# Adafruit_TMP117_angle.net
KiCad netlist of a schematic drawn in EAGLE
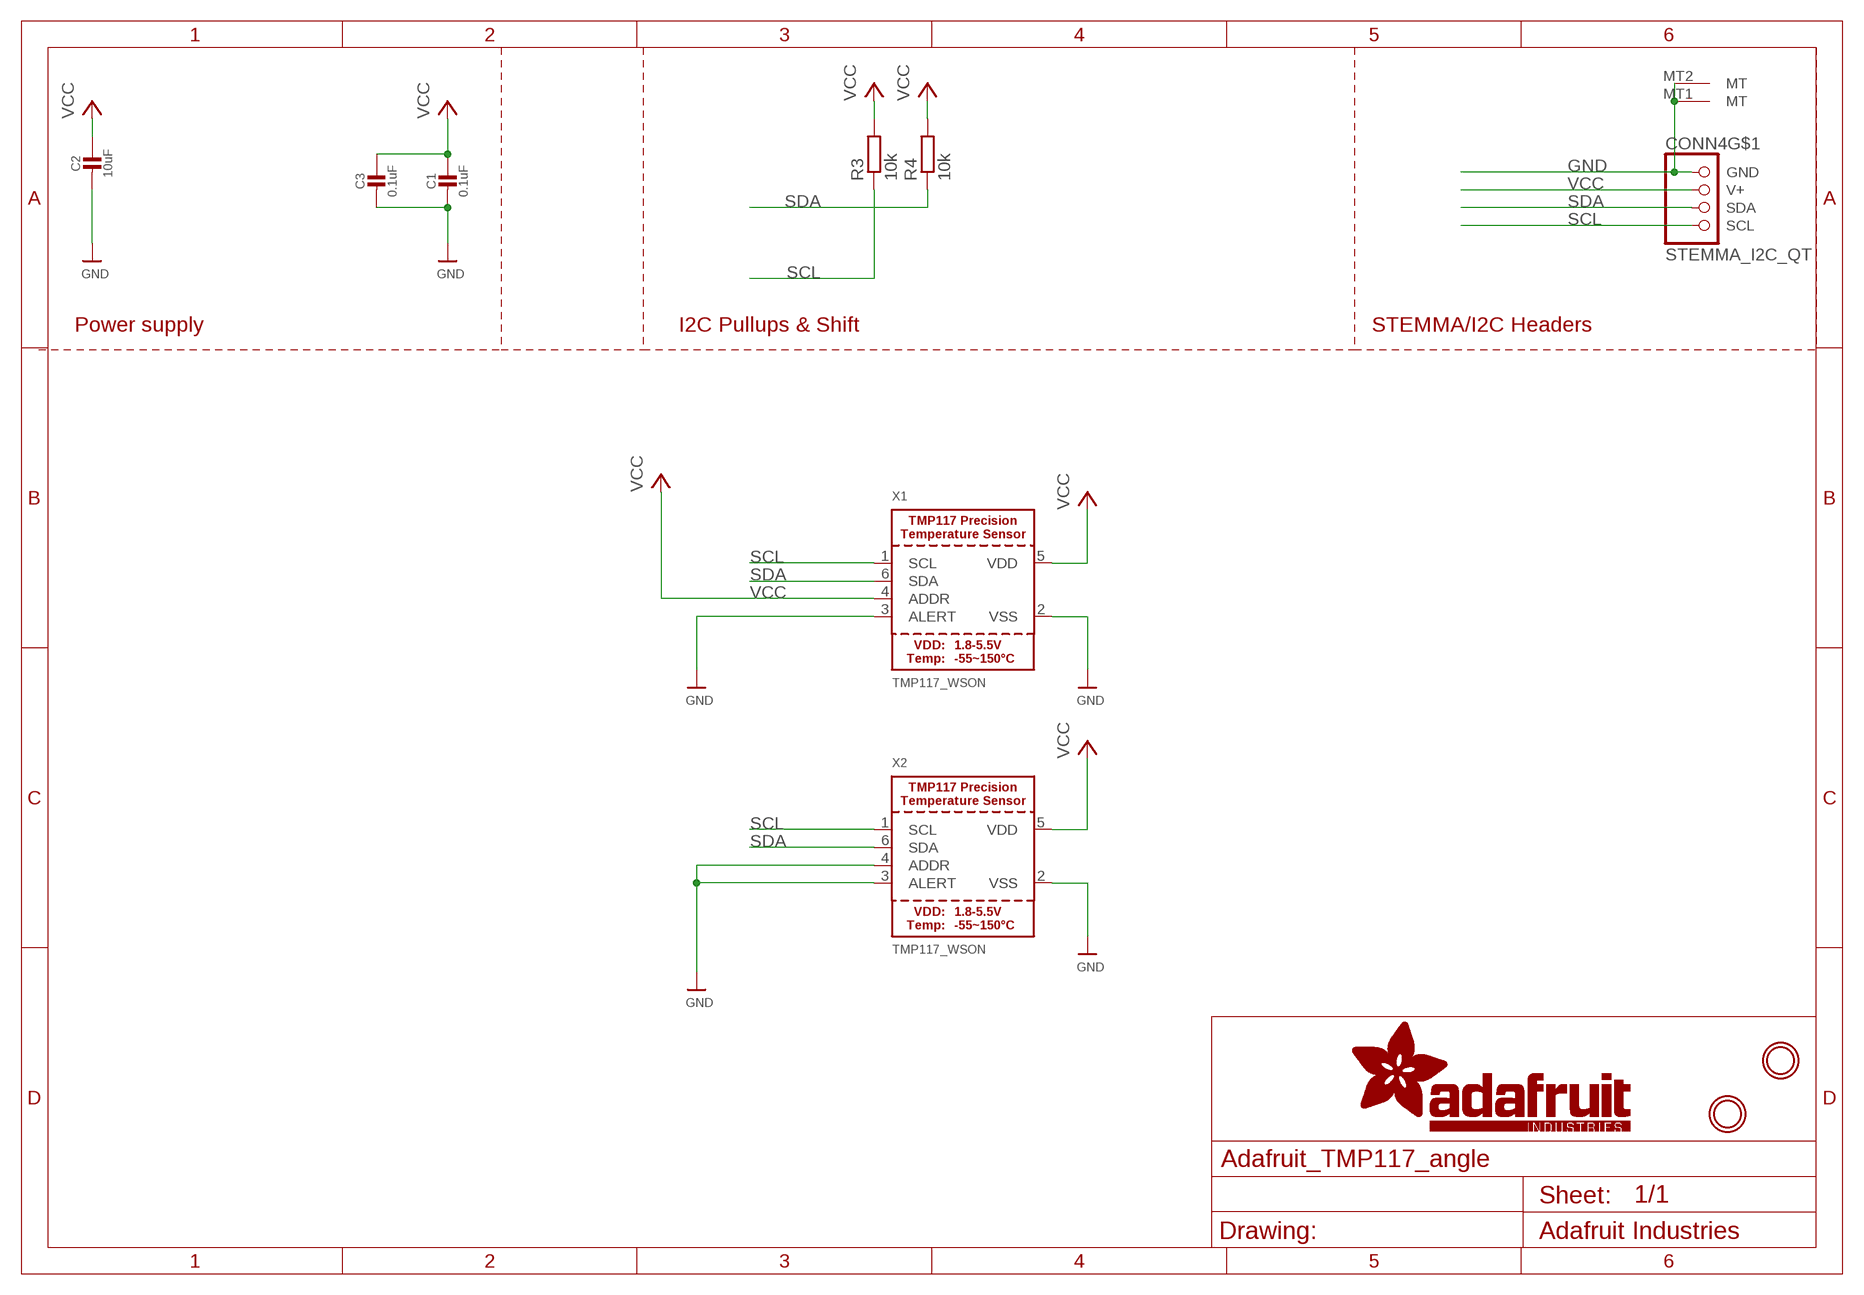
[diagram p0: schematic, sheet 1]

(export (version "E")
  (design (tool "Eeschema 10.0.6"))
  (components
    (comp (ref "C1")
      (value "0.1uF")
      (footprint "eagle-import:_0402")
      (libsource (lib "eagle-import") (part "CAP_CERAMIC_0402"))
    )
    (comp (ref "C2")
      (value "10uF")
      (footprint "eagle-import:_0603")
      (libsource (lib "eagle-import") (part "CAP_CERAMIC_0603"))
    )
    (comp (ref "C3")
      (value "0.1uF")
      (footprint "eagle-import:_0402")
      (libsource (lib "eagle-import") (part "CAP_CERAMIC_0402"))
    )
    (comp (ref "CONN4")
      (value "STEMMA_I2C_QT")
      (footprint "eagle-import:JST_SH4")
      (libsource (lib "eagle-import") (part "STEMMA_I2C_QT"))
    )
    (comp (ref "R3")
      (value "10k")
      (footprint "eagle-import:R0402")
      (libsource (lib "eagle-import") (part "R-EU_R0402"))
    )
    (comp (ref "R4")
      (value "10k")
      (footprint "eagle-import:R0402")
      (libsource (lib "eagle-import") (part "R-EU_R0402"))
    )
    (comp (ref "U$1")
      (value "MOUNTINGHOLE2.5")
      (footprint "eagle-import:MOUNTINGHOLE_2.5_PLATED")
      (libsource (lib "eagle-import") (part "MOUNTINGHOLE2.5"))
    )
    (comp (ref "U$19")
      (value "MOUNTINGHOLE2.5")
      (footprint "eagle-import:MOUNTINGHOLE_2.5_PLATED")
      (libsource (lib "eagle-import") (part "MOUNTINGHOLE2.5"))
    )
    (comp (ref "X1")
      (value "TMP117_WSON")
      (footprint "eagle-import:WSON-6")
      (libsource (lib "eagle-import") (part "TMP117_WSON"))
    )
    (comp (ref "X2")
      (value "TMP117_WSON")
      (footprint "eagle-import:WSON-6")
      (libsource (lib "eagle-import") (part "TMP117_WSON"))
    )
  )
  (nets
    (net (code "1") (name "/SCL") (class "Default")
      (node (ref "CONN4") (pin "4") (pinfunction "SCL_4") (pintype "passive"))
      (node (ref "R3") (pin "1") (pinfunction "1_1") (pintype "passive"))
      (node (ref "X1") (pin "1") (pinfunction "SCL_1") (pintype "bidirectional"))
      (node (ref "X2") (pin "1") (pinfunction "SCL_1") (pintype "bidirectional"))
    )
    (net (code "2") (name "/SDA") (class "Default")
      (node (ref "CONN4") (pin "3") (pinfunction "SDA_3") (pintype "passive"))
      (node (ref "R4") (pin "1") (pinfunction "1_1") (pintype "passive"))
      (node (ref "X1") (pin "6") (pinfunction "SDA_6") (pintype "bidirectional"))
      (node (ref "X2") (pin "6") (pinfunction "SDA_6") (pintype "bidirectional"))
    )
    (net (code "3") (name "GND") (class "Default")
      (node (ref "C1") (pin "2") (pinfunction "2_2") (pintype "passive"))
      (node (ref "C2") (pin "2") (pinfunction "2_2") (pintype "passive"))
      (node (ref "C3") (pin "2") (pinfunction "2_2") (pintype "passive"))
      (node (ref "CONN4") (pin "1") (pinfunction "GND_1") (pintype "passive"))
      (node (ref "CONN4") (pin "MT1") (pinfunction "MT_MT1") (pintype "bidirectional"))
      (node (ref "CONN4") (pin "MT2") (pinfunction "MT_MT2") (pintype "bidirectional"))
      (node (ref "X1") (pin "2") (pinfunction "VSS_2") (pintype "power_in"))
      (node (ref "X1") (pin "3") (pinfunction "ALERT_3") (pintype "output"))
      (node (ref "X2") (pin "2") (pinfunction "VSS_2") (pintype "power_in"))
      (node (ref "X2") (pin "3") (pinfunction "ALERT_3") (pintype "output"))
      (node (ref "X2") (pin "4") (pinfunction "ADDR_4") (pintype "input"))
    )
    (net (code "4") (name "VCC") (class "Default")
      (node (ref "C1") (pin "1") (pinfunction "1_1") (pintype "passive"))
      (node (ref "C2") (pin "1") (pinfunction "1_1") (pintype "passive"))
      (node (ref "C3") (pin "1") (pinfunction "1_1") (pintype "passive"))
      (node (ref "CONN4") (pin "2") (pinfunction "V+_2") (pintype "passive"))
      (node (ref "R3") (pin "2") (pinfunction "2_2") (pintype "passive"))
      (node (ref "R4") (pin "2") (pinfunction "2_2") (pintype "passive"))
      (node (ref "X1") (pin "4") (pinfunction "ADDR_4") (pintype "input"))
      (node (ref "X1") (pin "5") (pinfunction "VDD_5") (pintype "power_in"))
      (node (ref "X2") (pin "5") (pinfunction "VDD_5") (pintype "power_in"))
    )
  )
)
